# PowerStage.net
KiCad netlist of a schematic drawn in EAGLE
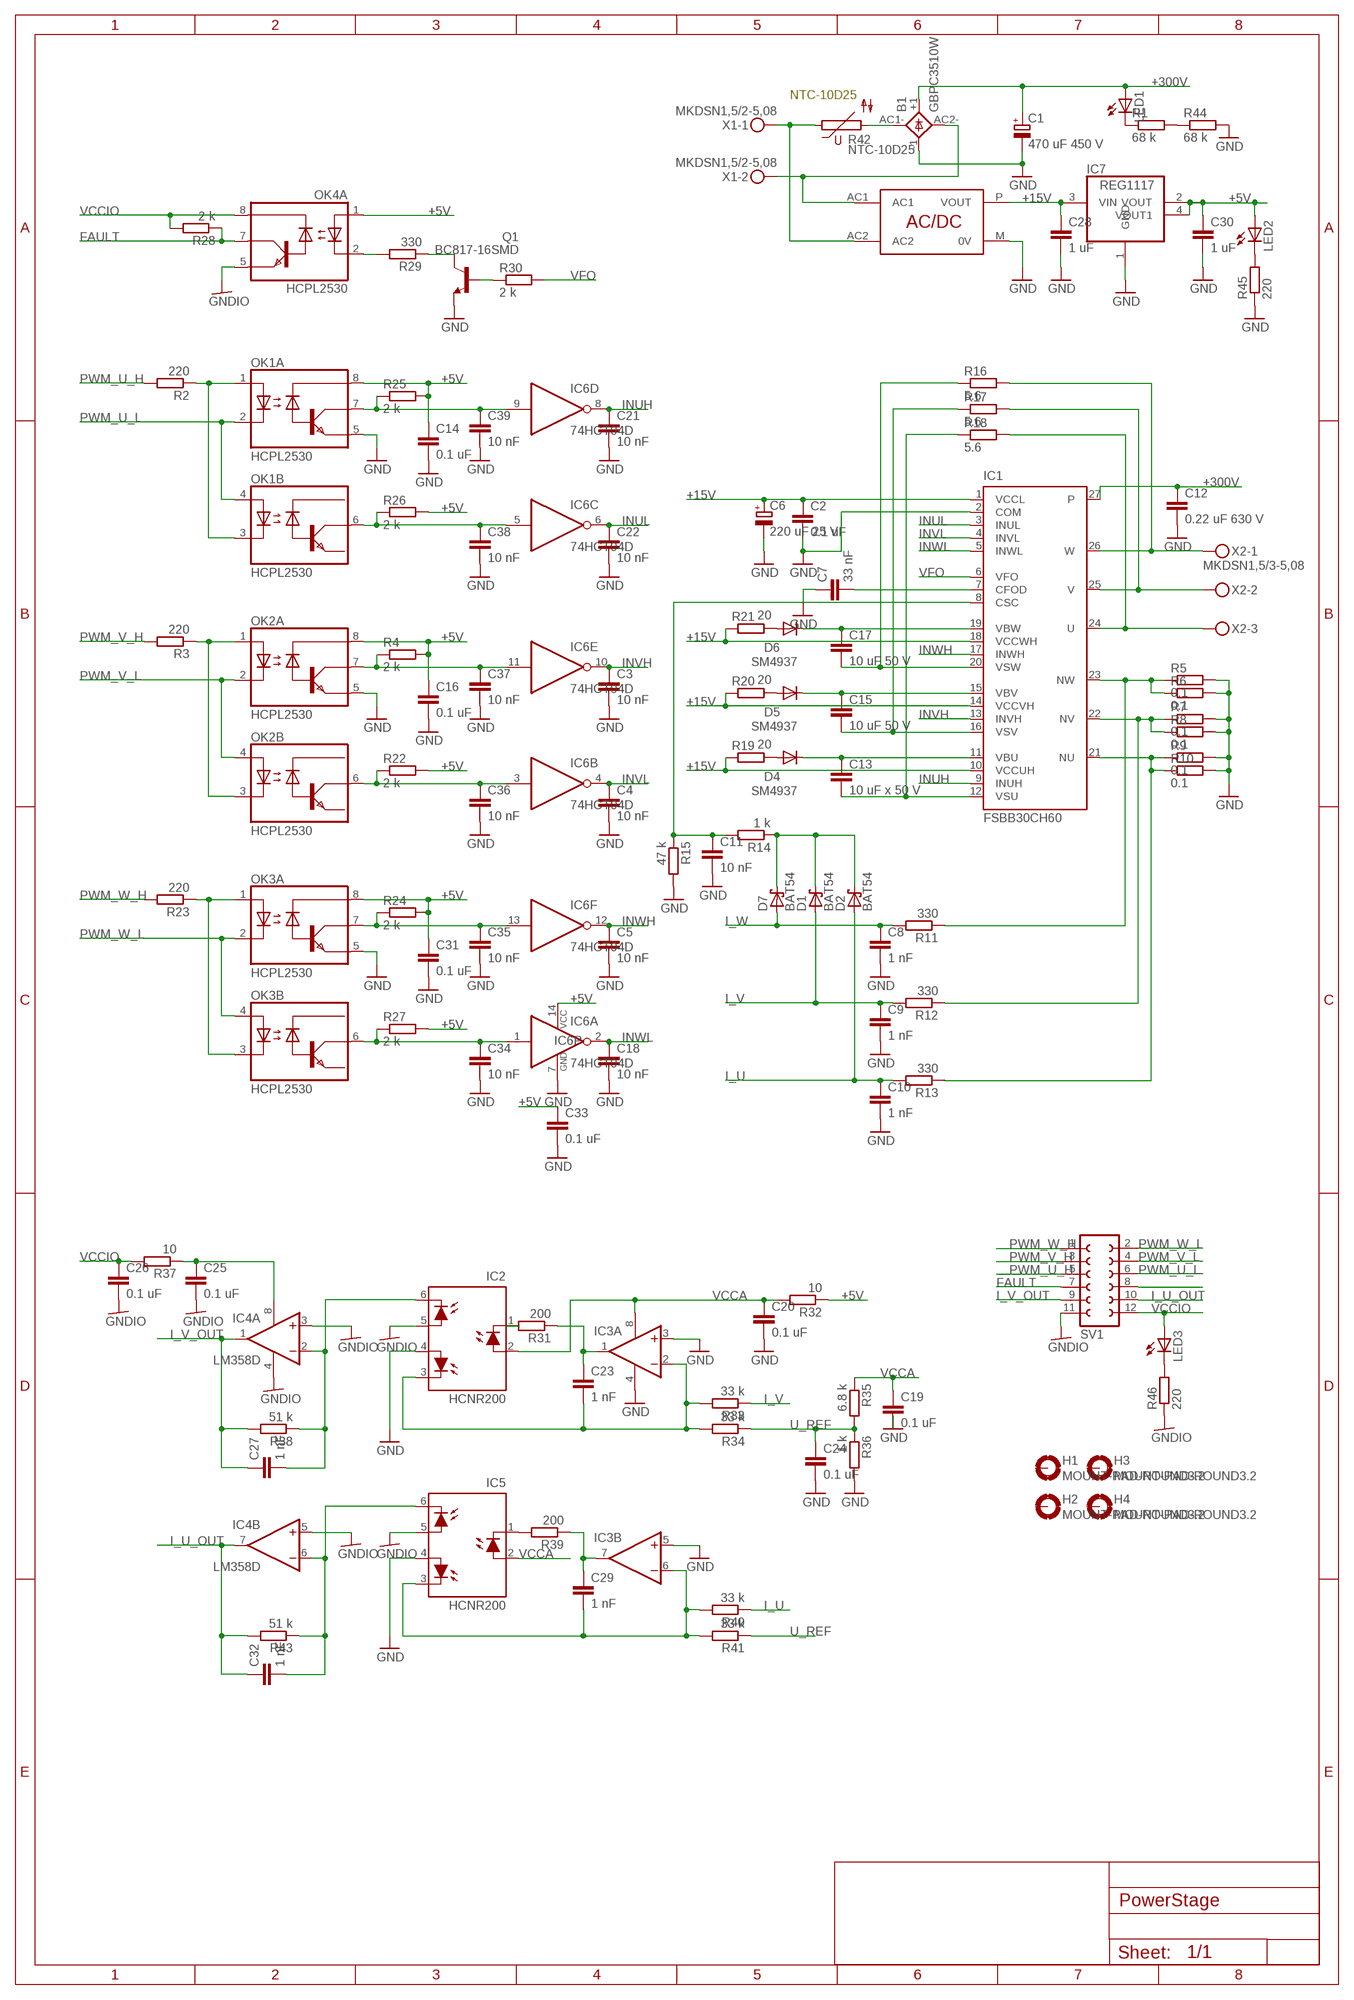
[diagram p0: schematic, sheet 1]

(export (version "E")
  (design (tool "Eeschema 10.0.6"))
  (components
    (comp (ref "B1")
      (value "GBPC3510W")
      (footprint "eagle-import:GBPC-W")
      (libsource (lib "eagle-import") (part "GBPC-W"))
    )
    (comp (ref "C1")
      (value "470 uF 450 V")
      (footprint "eagle-import:EB35D")
      (libsource (lib "eagle-import") (part "CPOL-EUE10-35"))
    )
    (comp (ref "C2")
      (value "0.1 uF")
      (footprint "eagle-import:C0603")
      (libsource (lib "eagle-import") (part "C-EUC0603"))
    )
    (comp (ref "C3")
      (value "10 nF")
      (footprint "eagle-import:C0603")
      (libsource (lib "eagle-import") (part "C-EUC0603"))
    )
    (comp (ref "C4")
      (value "10 nF")
      (footprint "eagle-import:C0603")
      (libsource (lib "eagle-import") (part "C-EUC0603"))
    )
    (comp (ref "C5")
      (value "10 nF")
      (footprint "eagle-import:C0603")
      (libsource (lib "eagle-import") (part "C-EUC0603"))
    )
    (comp (ref "C6")
      (value "220 uF 25 V")
      (footprint "eagle-import:PANASONIC_G")
      (libsource (lib "eagle-import") (part "CPOL-EUG"))
    )
    (comp (ref "C7")
      (value "33 nF")
      (footprint "eagle-import:C0603")
      (libsource (lib "eagle-import") (part "C-EUC0603"))
    )
    (comp (ref "C8")
      (value "1 nF")
      (footprint "eagle-import:C0603")
      (libsource (lib "eagle-import") (part "C-EUC0603"))
    )
    (comp (ref "C9")
      (value "1 nF")
      (footprint "eagle-import:C0603")
      (libsource (lib "eagle-import") (part "C-EUC0603"))
    )
    (comp (ref "C10")
      (value "1 nF")
      (footprint "eagle-import:C0603")
      (libsource (lib "eagle-import") (part "C-EUC0603"))
    )
    (comp (ref "C11")
      (value "10 nF")
      (footprint "eagle-import:C0603")
      (libsource (lib "eagle-import") (part "C-EUC0603"))
    )
    (comp (ref "C12")
      (value "0.22 uF 630 V")
      (footprint "eagle-import:C150-091X182")
      (libsource (lib "eagle-import") (part "C-EU150-091X182"))
    )
    (comp (ref "C13")
      (value "10 uF x 50 V")
      (footprint "eagle-import:C1210")
      (libsource (lib "eagle-import") (part "C-EUC1210"))
    )
    (comp (ref "C14")
      (value "0.1 uF")
      (footprint "eagle-import:C0603")
      (libsource (lib "eagle-import") (part "C-EUC0603"))
    )
    (comp (ref "C15")
      (value "10 uF 50 V")
      (footprint "eagle-import:C1210")
      (libsource (lib "eagle-import") (part "C-EUC1210"))
    )
    (comp (ref "C16")
      (value "0.1 uF")
      (footprint "eagle-import:C0603")
      (libsource (lib "eagle-import") (part "C-EUC0603"))
    )
    (comp (ref "C17")
      (value "10 uF 50 V")
      (footprint "eagle-import:C1210")
      (libsource (lib "eagle-import") (part "C-EUC1210"))
    )
    (comp (ref "C18")
      (value "10 nF")
      (footprint "eagle-import:C0603")
      (libsource (lib "eagle-import") (part "C-EUC0603"))
    )
    (comp (ref "C19")
      (value "0.1 uF")
      (footprint "eagle-import:C0603")
      (libsource (lib "eagle-import") (part "C-EUC0603"))
    )
    (comp (ref "C20")
      (value "0.1 uF")
      (footprint "eagle-import:C0603")
      (libsource (lib "eagle-import") (part "C-EUC0603"))
    )
    (comp (ref "C21")
      (value "10 nF")
      (footprint "eagle-import:C0603")
      (libsource (lib "eagle-import") (part "C-EUC0603"))
    )
    (comp (ref "C22")
      (value "10 nF")
      (footprint "eagle-import:C0603")
      (libsource (lib "eagle-import") (part "C-EUC0603"))
    )
    (comp (ref "C23")
      (value "1 nF")
      (footprint "eagle-import:C0603")
      (libsource (lib "eagle-import") (part "C-EUC0603"))
    )
    (comp (ref "C24")
      (value "0.1 uF")
      (footprint "eagle-import:C0603")
      (libsource (lib "eagle-import") (part "C-EUC0603"))
    )
    (comp (ref "C25")
      (value "0.1 uF")
      (footprint "eagle-import:C0603")
      (libsource (lib "eagle-import") (part "C-EUC0603"))
    )
    (comp (ref "C26")
      (value "0.1 uF")
      (footprint "eagle-import:C0603")
      (libsource (lib "eagle-import") (part "C-EUC0603"))
    )
    (comp (ref "C27")
      (value "1 nF")
      (footprint "eagle-import:C0603")
      (libsource (lib "eagle-import") (part "C-EUC0603"))
    )
    (comp (ref "C28")
      (value "1 uF")
      (footprint "eagle-import:C0603")
      (libsource (lib "eagle-import") (part "C-EUC0603"))
    )
    (comp (ref "C29")
      (value "1 nF")
      (footprint "eagle-import:C0603")
      (libsource (lib "eagle-import") (part "C-EUC0603"))
    )
    (comp (ref "C30")
      (value "1 uF")
      (footprint "eagle-import:C0603")
      (libsource (lib "eagle-import") (part "C-EUC0603"))
    )
    (comp (ref "C31")
      (value "0.1 uF")
      (footprint "eagle-import:C0603")
      (libsource (lib "eagle-import") (part "C-EUC0603"))
    )
    (comp (ref "C32")
      (value "1 nF")
      (footprint "eagle-import:C0603")
      (libsource (lib "eagle-import") (part "C-EUC0603"))
    )
    (comp (ref "C33")
      (value "0.1 uF")
      (footprint "eagle-import:C0603")
      (libsource (lib "eagle-import") (part "C-EUC0603"))
    )
    (comp (ref "C34")
      (value "10 nF")
      (footprint "eagle-import:C0603")
      (libsource (lib "eagle-import") (part "C-EUC0603"))
    )
    (comp (ref "C35")
      (value "10 nF")
      (footprint "eagle-import:C0603")
      (libsource (lib "eagle-import") (part "C-EUC0603"))
    )
    (comp (ref "C36")
      (value "10 nF")
      (footprint "eagle-import:C0603")
      (libsource (lib "eagle-import") (part "C-EUC0603"))
    )
    (comp (ref "C37")
      (value "10 nF")
      (footprint "eagle-import:C0603")
      (libsource (lib "eagle-import") (part "C-EUC0603"))
    )
    (comp (ref "C38")
      (value "10 nF")
      (footprint "eagle-import:C0603")
      (libsource (lib "eagle-import") (part "C-EUC0603"))
    )
    (comp (ref "C39")
      (value "10 nF")
      (footprint "eagle-import:C0603")
      (libsource (lib "eagle-import") (part "C-EUC0603"))
    )
    (comp (ref "D1")
      (value "BAT54")
      (footprint "eagle-import:SOT23")
      (libsource (lib "eagle-import") (part "BAT54"))
    )
    (comp (ref "D2")
      (value "BAT54")
      (footprint "eagle-import:SOT23")
      (libsource (lib "eagle-import") (part "BAT54"))
    )
    (comp (ref "D4")
      (value "SM4937")
      (footprint "eagle-import:MELF-MLL41")
      (libsource (lib "eagle-import") (part "DIODE-MELF-MLL41"))
    )
    (comp (ref "D5")
      (value "SM4937")
      (footprint "eagle-import:MELF-MLL41")
      (libsource (lib "eagle-import") (part "DIODE-MELF-MLL41"))
    )
    (comp (ref "D6")
      (value "SM4937")
      (footprint "eagle-import:MELF-MLL41")
      (libsource (lib "eagle-import") (part "DIODE-MELF-MLL41"))
    )
    (comp (ref "D7")
      (value "BAT54")
      (footprint "eagle-import:SOT23")
      (libsource (lib "eagle-import") (part "BAT54"))
    )
    (comp (ref "H1")
      (value "MOUNT-PAD-ROUND3.2")
      (footprint "eagle-import:3,2-PAD")
      (libsource (lib "eagle-import") (part "MOUNT-PAD-ROUND3.2"))
    )
    (comp (ref "H2")
      (value "MOUNT-PAD-ROUND3.2")
      (footprint "eagle-import:3,2-PAD")
      (libsource (lib "eagle-import") (part "MOUNT-PAD-ROUND3.2"))
    )
    (comp (ref "H3")
      (value "MOUNT-PAD-ROUND3.2")
      (footprint "eagle-import:3,2-PAD")
      (libsource (lib "eagle-import") (part "MOUNT-PAD-ROUND3.2"))
    )
    (comp (ref "H4")
      (value "MOUNT-PAD-ROUND3.2")
      (footprint "eagle-import:3,2-PAD")
      (libsource (lib "eagle-import") (part "MOUNT-PAD-ROUND3.2"))
    )
    (comp (ref "IC1")
      (value "FSBB30CH60")
      (footprint "eagle-import:FSBB30CH60")
      (fields (field (name "MPN") "FSBB30CH60B"))
      (libsource (lib "eagle-import") (part "FSBB30CH60"))
    )
    (comp (ref "IC2")
      (value "HCNR200")
      (footprint "eagle-import:DIL08-400")
      (libsource (lib "eagle-import") (part "HCNR200"))
    )
    (comp (ref "IC3")
      (value "2AMP_P8+4D")
      (footprint "eagle-import:SO08")
      (libsource (lib "eagle-import") (part "2AMP_P8+4D"))
    )
    (comp (ref "IC4")
      (value "LM358D")
      (footprint "eagle-import:SO08")
      (libsource (lib "eagle-import") (part "LM358D"))
    )
    (comp (ref "IC5")
      (value "HCNR200")
      (footprint "eagle-import:DIL08-400")
      (libsource (lib "eagle-import") (part "HCNR200"))
    )
    (comp (ref "IC6")
      (value "74HCT04D")
      (footprint "eagle-import:SO14")
      (libsource (lib "eagle-import") (part "7404DHCT"))
    )
    (comp (ref "IC7")
      (value "REG1117")
      (footprint "eagle-import:SOT223")
      (libsource (lib "eagle-import") (part "REG1117"))
    )
    (comp (ref "LED1")
      (value "LEDCHIP-LED0603")
      (footprint "eagle-import:CHIP-LED0603")
      (libsource (lib "eagle-import") (part "LEDCHIP-LED0603"))
    )
    (comp (ref "LED2")
      (value "LEDCHIP-LED0603")
      (footprint "eagle-import:CHIP-LED0603")
      (libsource (lib "eagle-import") (part "LEDCHIP-LED0603"))
    )
    (comp (ref "LED3")
      (value "LEDCHIP-LED0603")
      (footprint "eagle-import:CHIP-LED0603")
      (libsource (lib "eagle-import") (part "LEDCHIP-LED0603"))
    )
    (comp (ref "OK1")
      (value "HCPL2530")
      (footprint "eagle-import:DIL08")
      (fields (field (name "MF") "AGILENT TECHNOLOGIES") (field (name "MPN") "HCPL-2530-000E"))
      (libsource (lib "eagle-import") (part "HCPL2530"))
    )
    (comp (ref "OK2")
      (value "HCPL2530")
      (footprint "eagle-import:DIL08")
      (fields (field (name "MF") "AGILENT TECHNOLOGIES") (field (name "MPN") "HCPL-2530-000E"))
      (libsource (lib "eagle-import") (part "HCPL2530"))
    )
    (comp (ref "OK3")
      (value "HCPL2530")
      (footprint "eagle-import:DIL08")
      (fields (field (name "MF") "AGILENT TECHNOLOGIES") (field (name "MPN") "HCPL-2530-000E"))
      (libsource (lib "eagle-import") (part "HCPL2530"))
    )
    (comp (ref "OK4")
      (value "HCPL2530")
      (footprint "eagle-import:DIL08")
      (fields (field (name "MF") "AGILENT TECHNOLOGIES") (field (name "MPN") "HCPL-2530-000E"))
      (libsource (lib "eagle-import") (part "HCPL2530"))
    )
    (comp (ref "Q1")
      (value "BC817-16SMD")
      (footprint "eagle-import:SOT23-BEC")
      (libsource (lib "eagle-import") (part "BC817SMD-16"))
    )
    (comp (ref "R1")
      (value "68 k")
      (footprint "eagle-import:R1206")
      (libsource (lib "eagle-import") (part "resistor_R-EU_R1206"))
    )
    (comp (ref "R2")
      (value "220")
      (footprint "eagle-import:R0603")
      (libsource (lib "eagle-import") (part "R-EU_R0603"))
    )
    (comp (ref "R3")
      (value "220")
      (footprint "eagle-import:R0603")
      (libsource (lib "eagle-import") (part "R-EU_R0603"))
    )
    (comp (ref "R4")
      (value "2 k")
      (footprint "eagle-import:R0603")
      (libsource (lib "eagle-import") (part "R-EU_R0603"))
    )
    (comp (ref "R5")
      (value "0.1")
      (footprint "eagle-import:R2512")
      (libsource (lib "eagle-import") (part "R-EU_R2512"))
    )
    (comp (ref "R6")
      (value "0.1")
      (footprint "eagle-import:R2512")
      (libsource (lib "eagle-import") (part "R-EU_R2512"))
    )
    (comp (ref "R7")
      (value "0.1")
      (footprint "eagle-import:R2512")
      (libsource (lib "eagle-import") (part "R-EU_R2512"))
    )
    (comp (ref "R8")
      (value "0.1")
      (footprint "eagle-import:R2512")
      (libsource (lib "eagle-import") (part "R-EU_R2512"))
    )
    (comp (ref "R9")
      (value "0.1")
      (footprint "eagle-import:R2512")
      (libsource (lib "eagle-import") (part "R-EU_R2512"))
    )
    (comp (ref "R10")
      (value "0.1")
      (footprint "eagle-import:R2512")
      (libsource (lib "eagle-import") (part "R-EU_R2512"))
    )
    (comp (ref "R11")
      (value "330")
      (footprint "eagle-import:R0603")
      (libsource (lib "eagle-import") (part "R-EU_R0603"))
    )
    (comp (ref "R12")
      (value "330")
      (footprint "eagle-import:R0603")
      (libsource (lib "eagle-import") (part "R-EU_R0603"))
    )
    (comp (ref "R13")
      (value "330")
      (footprint "eagle-import:R0603")
      (libsource (lib "eagle-import") (part "R-EU_R0603"))
    )
    (comp (ref "R14")
      (value "1 k")
      (footprint "eagle-import:R0603")
      (libsource (lib "eagle-import") (part "R-EU_R0603"))
    )
    (comp (ref "R15")
      (value "47 k")
      (footprint "eagle-import:R0603")
      (libsource (lib "eagle-import") (part "R-EU_R0603"))
    )
    (comp (ref "R16")
      (value "5.6")
      (footprint "eagle-import:R1206")
      (libsource (lib "eagle-import") (part "R-EU_R1206"))
    )
    (comp (ref "R17")
      (value "5.6")
      (footprint "eagle-import:R1206")
      (libsource (lib "eagle-import") (part "R-EU_R1206"))
    )
    (comp (ref "R18")
      (value "5.6")
      (footprint "eagle-import:R1206")
      (libsource (lib "eagle-import") (part "R-EU_R1206"))
    )
    (comp (ref "R19")
      (value "20")
      (footprint "eagle-import:R1206")
      (libsource (lib "eagle-import") (part "R-EU_R1206"))
    )
    (comp (ref "R20")
      (value "20")
      (footprint "eagle-import:R1206")
      (libsource (lib "eagle-import") (part "R-EU_R1206"))
    )
    (comp (ref "R21")
      (value "20")
      (footprint "eagle-import:R1206")
      (libsource (lib "eagle-import") (part "R-EU_R1206"))
    )
    (comp (ref "R22")
      (value "2 k")
      (footprint "eagle-import:R0603")
      (libsource (lib "eagle-import") (part "R-EU_R0603"))
    )
    (comp (ref "R23")
      (value "220")
      (footprint "eagle-import:R0603")
      (libsource (lib "eagle-import") (part "R-EU_R0603"))
    )
    (comp (ref "R24")
      (value "2 k")
      (footprint "eagle-import:R0603")
      (libsource (lib "eagle-import") (part "R-EU_R0603"))
    )
    (comp (ref "R25")
      (value "2 k")
      (footprint "eagle-import:R0603")
      (libsource (lib "eagle-import") (part "R-EU_R0603"))
    )
    (comp (ref "R26")
      (value "2 k")
      (footprint "eagle-import:R0603")
      (libsource (lib "eagle-import") (part "R-EU_R0603"))
    )
    (comp (ref "R27")
      (value "2 k")
      (footprint "eagle-import:R0603")
      (libsource (lib "eagle-import") (part "R-EU_R0603"))
    )
    (comp (ref "R28")
      (value "2 k")
      (footprint "eagle-import:R0603")
      (libsource (lib "eagle-import") (part "R-EU_R0603"))
    )
    (comp (ref "R29")
      (value "330")
      (footprint "eagle-import:R0603")
      (libsource (lib "eagle-import") (part "R-EU_R0603"))
    )
    (comp (ref "R30")
      (value "2 k")
      (footprint "eagle-import:R0603")
      (libsource (lib "eagle-import") (part "R-EU_R0603"))
    )
    (comp (ref "R31")
      (value "200")
      (footprint "eagle-import:R0603")
      (libsource (lib "eagle-import") (part "R-EU_R0603"))
    )
    (comp (ref "R32")
      (value "10")
      (footprint "eagle-import:R0603")
      (libsource (lib "eagle-import") (part "R-EU_R0603"))
    )
    (comp (ref "R33")
      (value "33 k")
      (footprint "eagle-import:R0603")
      (libsource (lib "eagle-import") (part "R-EU_R0603"))
    )
    (comp (ref "R34")
      (value "33 k")
      (footprint "eagle-import:R0603")
      (libsource (lib "eagle-import") (part "R-EU_R0603"))
    )
    (comp (ref "R35")
      (value "6.8 k")
      (footprint "eagle-import:R0603")
      (libsource (lib "eagle-import") (part "R-EU_R0603"))
    )
    (comp (ref "R36")
      (value "1 k")
      (footprint "eagle-import:R0603")
      (libsource (lib "eagle-import") (part "R-EU_R0603"))
    )
    (comp (ref "R37")
      (value "10")
      (footprint "eagle-import:R0603")
      (libsource (lib "eagle-import") (part "R-EU_R0603"))
    )
    (comp (ref "R38")
      (value "51 k")
      (footprint "eagle-import:R0603")
      (libsource (lib "eagle-import") (part "R-EU_R0603"))
    )
    (comp (ref "R39")
      (value "200")
      (footprint "eagle-import:R0603")
      (libsource (lib "eagle-import") (part "R-EU_R0603"))
    )
    (comp (ref "R40")
      (value "33 k")
      (footprint "eagle-import:R0603")
      (libsource (lib "eagle-import") (part "R-EU_R0603"))
    )
    (comp (ref "R41")
      (value "33 k")
      (footprint "eagle-import:R0603")
      (libsource (lib "eagle-import") (part "R-EU_R0603"))
    )
    (comp (ref "R42")
      (value "NTC-10D25")
      (footprint "eagle-import:S20K40")
      (libsource (lib "eagle-import") (part "S20K40"))
    )
    (comp (ref "R43")
      (value "51 k")
      (footprint "eagle-import:R0603")
      (libsource (lib "eagle-import") (part "R-EU_R0603"))
    )
    (comp (ref "R44")
      (value "68 k")
      (footprint "eagle-import:R1206")
      (libsource (lib "eagle-import") (part "resistor_R-EU_R1206"))
    )
    (comp (ref "R45")
      (value "220")
      (footprint "eagle-import:R0603")
      (libsource (lib "eagle-import") (part "R-EU_R0603"))
    )
    (comp (ref "R46")
      (value "220")
      (footprint "eagle-import:R0603")
      (libsource (lib "eagle-import") (part "R-EU_R0603"))
    )
    (comp (ref "SV1")
      (value "FE06-2")
      (footprint "eagle-import:FE06-2")
      (libsource (lib "eagle-import") (part "FE06-2"))
    )
    (comp (ref "U$1")
      (value "KUUKO_090873")
      (footprint "eagle-import:KUUKO_090873")
      (libsource (lib "eagle-import") (part "KUUKO_090873"))
    )
    (comp (ref "X1")
      (value "MKDSN1,5/2-5,08")
      (footprint "eagle-import:MKDSN1,5_2-5,08")
      (fields (field (name "MPN") "MKDSN 1,5/2-5.08"))
      (libsource (lib "eagle-import") (part "MKDSN1,5/2-5,08"))
    )
    (comp (ref "X2")
      (value "MKDSN1,5/3-5,08")
      (footprint "eagle-import:MKDSN1,5_3-5,08")
      (fields (field (name "MPN") "SMKDSN1,5/3-5,08"))
      (libsource (lib "eagle-import") (part "MKDSN1,5/3-5,08"))
    )
  )
  (nets
    (net (code "1") (name "/+5V") (class "Default")
      (node (ref "C14") (pin "1") (pinfunction "1_1") (pintype "passive"))
      (node (ref "C16") (pin "1") (pinfunction "1_1") (pintype "passive"))
      (node (ref "C30") (pin "1") (pinfunction "1_1") (pintype "passive"))
      (node (ref "C31") (pin "1") (pinfunction "1_1") (pintype "passive"))
      (node (ref "C33") (pin "1") (pinfunction "1_1") (pintype "passive"))
      (node (ref "IC6") (pin "14") (pinfunction "VCC_14") (pintype "power_in"))
      (node (ref "IC7") (pin "2") (pinfunction "VOUT_2") (pintype "output"))
      (node (ref "IC7") (pin "4") (pinfunction "VOUT1_4") (pintype "output"))
      (node (ref "LED2") (pin "A") (pinfunction "A_A") (pintype "passive"))
      (node (ref "OK1") (pin "8") (pinfunction "VCC_8") (pintype "passive"))
      (node (ref "OK2") (pin "8") (pinfunction "VCC_8") (pintype "passive"))
      (node (ref "OK3") (pin "8") (pinfunction "VCC_8") (pintype "passive"))
      (node (ref "OK4") (pin "1") (pinfunction "A1_1") (pintype "passive"))
      (node (ref "R22") (pin "2") (pinfunction "2_2") (pintype "passive"))
      (node (ref "R24") (pin "2") (pinfunction "2_2") (pintype "passive"))
      (node (ref "R25") (pin "2") (pinfunction "2_2") (pintype "passive"))
      (node (ref "R26") (pin "2") (pinfunction "2_2") (pintype "passive"))
      (node (ref "R27") (pin "2") (pinfunction "2_2") (pintype "passive"))
      (node (ref "R32") (pin "1") (pinfunction "1_1") (pintype "passive"))
      (node (ref "R4") (pin "2") (pinfunction "2_2") (pintype "passive"))
    )
    (net (code "2") (name "/+15V") (class "Default")
      (node (ref "C2") (pin "1") (pinfunction "1_1") (pintype "passive"))
      (node (ref "C28") (pin "1") (pinfunction "1_1") (pintype "passive"))
      (node (ref "C6") (pin "+") (pinfunction "+_+") (pintype "passive"))
      (node (ref "IC1") (pin "1") (pinfunction "VCCL_1") (pintype "power_in"))
      (node (ref "IC1") (pin "10") (pinfunction "VCCUH_10") (pintype "input"))
      (node (ref "IC1") (pin "14") (pinfunction "VCCVH_14") (pintype "input"))
      (node (ref "IC1") (pin "18") (pinfunction "VCCWH_18") (pintype "input"))
      (node (ref "IC7") (pin "3") (pinfunction "VIN_3") (pintype "input"))
      (node (ref "R19") (pin "1") (pinfunction "1_1") (pintype "passive"))
      (node (ref "R20") (pin "1") (pinfunction "1_1") (pintype "passive"))
      (node (ref "R21") (pin "1") (pinfunction "1_1") (pintype "passive"))
      (node (ref "U$1") (pin "P") (pinfunction "VOUT_P") (pintype "bidirectional"))
    )
    (net (code "3") (name "/+300V") (class "Default")
      (node (ref "B1") (pin "+1") (pinfunction "+_+1") (pintype "passive"))
      (node (ref "C1") (pin "+") (pinfunction "+_+") (pintype "passive"))
      (node (ref "C12") (pin "1") (pinfunction "1_1") (pintype "passive"))
      (node (ref "IC1") (pin "27") (pinfunction "P_27") (pintype "input"))
      (node (ref "LED1") (pin "A") (pinfunction "A_A") (pintype "passive"))
    )
    (net (code "4") (name "/FAULT") (class "Default")
      (node (ref "OK4") (pin "7") (pinfunction "VO1_7") (pintype "passive"))
      (node (ref "R28") (pin "1") (pinfunction "1_1") (pintype "passive"))
      (node (ref "SV1") (pin "7") (pinfunction "7_7") (pintype "passive"))
    )
    (net (code "5") (name "/INUH") (class "Default")
      (node (ref "C21") (pin "1") (pinfunction "1_1") (pintype "passive"))
      (node (ref "IC1") (pin "9") (pinfunction "INUH_9") (pintype "input"))
      (node (ref "IC6") (pin "8") (pinfunction "O_8") (pintype "output"))
    )
    (net (code "6") (name "/INUL") (class "Default")
      (node (ref "C22") (pin "1") (pinfunction "1_1") (pintype "passive"))
      (node (ref "IC1") (pin "3") (pinfunction "INUL_3") (pintype "input"))
      (node (ref "IC6") (pin "6") (pinfunction "O_6") (pintype "output"))
    )
    (net (code "7") (name "/INVH") (class "Default")
      (node (ref "C3") (pin "1") (pinfunction "1_1") (pintype "passive"))
      (node (ref "IC1") (pin "13") (pinfunction "INVH_13") (pintype "input"))
      (node (ref "IC6") (pin "10") (pinfunction "O_10") (pintype "output"))
    )
    (net (code "8") (name "/INVL") (class "Default")
      (node (ref "C4") (pin "1") (pinfunction "1_1") (pintype "passive"))
      (node (ref "IC1") (pin "4") (pinfunction "INVL_4") (pintype "input"))
      (node (ref "IC6") (pin "4") (pinfunction "O_4") (pintype "output"))
    )
    (net (code "9") (name "/INWH") (class "Default")
      (node (ref "C5") (pin "1") (pinfunction "1_1") (pintype "passive"))
      (node (ref "IC1") (pin "17") (pinfunction "INWH_17") (pintype "input"))
      (node (ref "IC6") (pin "12") (pinfunction "O_12") (pintype "output"))
    )
    (net (code "10") (name "/INWL") (class "Default")
      (node (ref "C18") (pin "1") (pinfunction "1_1") (pintype "passive"))
      (node (ref "IC1") (pin "5") (pinfunction "INWL_5") (pintype "input"))
      (node (ref "IC6") (pin "2") (pinfunction "O_2") (pintype "output"))
    )
    (net (code "11") (name "/I_U") (class "Default")
      (node (ref "C10") (pin "1") (pinfunction "1_1") (pintype "passive"))
      (node (ref "D2") (pin "1") (pinfunction "A_1") (pintype "passive"))
      (node (ref "R13") (pin "2") (pinfunction "2_2") (pintype "passive"))
      (node (ref "R40") (pin "1") (pinfunction "1_1") (pintype "passive"))
    )
    (net (code "12") (name "/I_U_OUT") (class "Default")
      (node (ref "C32") (pin "1") (pinfunction "1_1") (pintype "passive"))
      (node (ref "IC4") (pin "7") (pinfunction "OUT_7") (pintype "output"))
      (node (ref "R43") (pin "2") (pinfunction "2_2") (pintype "passive"))
      (node (ref "SV1") (pin "10") (pinfunction "10_10") (pintype "passive"))
    )
    (net (code "13") (name "/I_V") (class "Default")
      (node (ref "C9") (pin "1") (pinfunction "1_1") (pintype "passive"))
      (node (ref "D1") (pin "1") (pinfunction "A_1") (pintype "passive"))
      (node (ref "R12") (pin "2") (pinfunction "2_2") (pintype "passive"))
      (node (ref "R33") (pin "1") (pinfunction "1_1") (pintype "passive"))
    )
    (net (code "14") (name "/I_V_OUT") (class "Default")
      (node (ref "C27") (pin "1") (pinfunction "1_1") (pintype "passive"))
      (node (ref "IC4") (pin "1") (pinfunction "OUT_1") (pintype "output"))
      (node (ref "R38") (pin "2") (pinfunction "2_2") (pintype "passive"))
      (node (ref "SV1") (pin "9") (pinfunction "9_9") (pintype "passive"))
    )
    (net (code "15") (name "/I_W") (class "Default")
      (node (ref "C8") (pin "1") (pinfunction "1_1") (pintype "passive"))
      (node (ref "D7") (pin "1") (pinfunction "A_1") (pintype "passive"))
      (node (ref "R11") (pin "2") (pinfunction "2_2") (pintype "passive"))
    )
    (net (code "16") (name "/PWM_U_H") (class "Default")
      (node (ref "R2") (pin "2") (pinfunction "2_2") (pintype "passive"))
      (node (ref "SV1") (pin "5") (pinfunction "5_5") (pintype "passive"))
    )
    (net (code "17") (name "/PWM_U_L") (class "Default")
      (node (ref "OK1") (pin "2") (pinfunction "C1_2") (pintype "passive"))
      (node (ref "OK1") (pin "4") (pinfunction "A2_4") (pintype "passive"))
      (node (ref "SV1") (pin "6") (pinfunction "6_6") (pintype "passive"))
    )
    (net (code "18") (name "/PWM_V_H") (class "Default")
      (node (ref "R3") (pin "2") (pinfunction "2_2") (pintype "passive"))
      (node (ref "SV1") (pin "3") (pinfunction "3_3") (pintype "passive"))
    )
    (net (code "19") (name "/PWM_V_L") (class "Default")
      (node (ref "OK2") (pin "2") (pinfunction "C1_2") (pintype "passive"))
      (node (ref "OK2") (pin "4") (pinfunction "A2_4") (pintype "passive"))
      (node (ref "SV1") (pin "4") (pinfunction "4_4") (pintype "passive"))
    )
    (net (code "20") (name "/PWM_W_H") (class "Default")
      (node (ref "R23") (pin "2") (pinfunction "2_2") (pintype "passive"))
      (node (ref "SV1") (pin "1") (pinfunction "1_1") (pintype "passive"))
    )
    (net (code "21") (name "/PWM_W_L") (class "Default")
      (node (ref "OK3") (pin "2") (pinfunction "C1_2") (pintype "passive"))
      (node (ref "OK3") (pin "4") (pinfunction "A2_4") (pintype "passive"))
      (node (ref "SV1") (pin "2") (pinfunction "2_2") (pintype "passive"))
    )
    (net (code "22") (name "/U_REF") (class "Default")
      (node (ref "C24") (pin "1") (pinfunction "1_1") (pintype "passive"))
      (node (ref "R34") (pin "1") (pinfunction "1_1") (pintype "passive"))
      (node (ref "R35") (pin "2") (pinfunction "2_2") (pintype "passive"))
      (node (ref "R36") (pin "1") (pinfunction "1_1") (pintype "passive"))
      (node (ref "R41") (pin "1") (pinfunction "1_1") (pintype "passive"))
    )
    (net (code "23") (name "/VCCA") (class "Default")
      (node (ref "C19") (pin "1") (pinfunction "1_1") (pintype "passive"))
      (node (ref "C20") (pin "1") (pinfunction "1_1") (pintype "passive"))
      (node (ref "IC2") (pin "2") (pinfunction "A_2") (pintype "passive"))
      (node (ref "IC3") (pin "8") (pinfunction "V+_8") (pintype "power_in"))
      (node (ref "IC5") (pin "2") (pinfunction "A_2") (pintype "passive"))
      (node (ref "R32") (pin "2") (pinfunction "2_2") (pintype "passive"))
      (node (ref "R35") (pin "1") (pinfunction "1_1") (pintype "passive"))
    )
    (net (code "24") (name "/VCCIO") (class "Default")
      (node (ref "C26") (pin "1") (pinfunction "1_1") (pintype "passive"))
      (node (ref "LED3") (pin "A") (pinfunction "A_A") (pintype "passive"))
      (node (ref "OK4") (pin "8") (pinfunction "VCC_8") (pintype "passive"))
      (node (ref "R28") (pin "2") (pinfunction "2_2") (pintype "passive"))
      (node (ref "R37") (pin "2") (pinfunction "2_2") (pintype "passive"))
      (node (ref "SV1") (pin "12") (pinfunction "12_12") (pintype "passive"))
    )
    (net (code "25") (name "/VFO") (class "Default")
      (node (ref "IC1") (pin "6") (pinfunction "VFO_6") (pintype "output"))
      (node (ref "R30") (pin "2") (pinfunction "2_2") (pintype "passive"))
    )
    (net (code "26") (name "GND") (class "Default")
      (node (ref "B1") (pin "-1") (pinfunction "-_-1") (pintype "passive"))
      (node (ref "C1") (pin "-") (pinfunction "-_-") (pintype "passive"))
      (node (ref "C10") (pin "2") (pinfunction "2_2") (pintype "passive"))
      (node (ref "C11") (pin "2") (pinfunction "2_2") (pintype "passive"))
      (node (ref "C12") (pin "2") (pinfunction "2_2") (pintype "passive"))
      (node (ref "C14") (pin "2") (pinfunction "2_2") (pintype "passive"))
      (node (ref "C16") (pin "2") (pinfunction "2_2") (pintype "passive"))
      (node (ref "C18") (pin "2") (pinfunction "2_2") (pintype "passive"))
      (node (ref "C19") (pin "2") (pinfunction "2_2") (pintype "passive"))
      (node (ref "C2") (pin "2") (pinfunction "2_2") (pintype "passive"))
      (node (ref "C20") (pin "2") (pinfunction "2_2") (pintype "passive"))
      (node (ref "C21") (pin "2") (pinfunction "2_2") (pintype "passive"))
      (node (ref "C22") (pin "2") (pinfunction "2_2") (pintype "passive"))
      (node (ref "C24") (pin "2") (pinfunction "2_2") (pintype "passive"))
      (node (ref "C28") (pin "2") (pinfunction "2_2") (pintype "passive"))
      (node (ref "C3") (pin "2") (pinfunction "2_2") (pintype "passive"))
      (node (ref "C30") (pin "2") (pinfunction "2_2") (pintype "passive"))
      (node (ref "C31") (pin "2") (pinfunction "2_2") (pintype "passive"))
      (node (ref "C33") (pin "2") (pinfunction "2_2") (pintype "passive"))
      (node (ref "C34") (pin "2") (pinfunction "2_2") (pintype "passive"))
      (node (ref "C35") (pin "2") (pinfunction "2_2") (pintype "passive"))
      (node (ref "C36") (pin "2") (pinfunction "2_2") (pintype "passive"))
      (node (ref "C37") (pin "2") (pinfunction "2_2") (pintype "passive"))
      (node (ref "C38") (pin "2") (pinfunction "2_2") (pintype "passive"))
      (node (ref "C39") (pin "2") (pinfunction "2_2") (pintype "passive"))
      (node (ref "C4") (pin "2") (pinfunction "2_2") (pintype "passive"))
      (node (ref "C5") (pin "2") (pinfunction "2_2") (pintype "passive"))
      (node (ref "C6") (pin "-") (pinfunction "-_-") (pintype "passive"))
      (node (ref "C7") (pin "1") (pinfunction "1_1") (pintype "passive"))
      (node (ref "C8") (pin "2") (pinfunction "2_2") (pintype "passive"))
      (node (ref "C9") (pin "2") (pinfunction "2_2") (pintype "passive"))
      (node (ref "IC1") (pin "2") (pinfunction "COM_2") (pintype "power_in"))
      (node (ref "IC2") (pin "4") (pinfunction "A1_4") (pintype "passive"))
      (node (ref "IC3") (pin "3") (pinfunction "+IN_3") (pintype "input"))
      (node (ref "IC3") (pin "4") (pinfunction "V-_4") (pintype "power_in"))
      (node (ref "IC3") (pin "5") (pinfunction "+IN_5") (pintype "input"))
      (node (ref "IC5") (pin "4") (pinfunction "A1_4") (pintype "passive"))
      (node (ref "IC6") (pin "7") (pinfunction "GND_7") (pintype "power_in"))
      (node (ref "IC7") (pin "1") (pinfunction "GND_1") (pintype "power_in"))
      (node (ref "OK1") (pin "5") (pinfunction "GND_5") (pintype "passive"))
      (node (ref "OK2") (pin "5") (pinfunction "GND_5") (pintype "passive"))
      (node (ref "OK3") (pin "5") (pinfunction "GND_5") (pintype "passive"))
      (node (ref "Q1") (pin "E") (pinfunction "E_E") (pintype "passive"))
      (node (ref "R10") (pin "2") (pinfunction "2_2") (pintype "passive"))
      (node (ref "R15") (pin "2") (pinfunction "2_2") (pintype "passive"))
      (node (ref "R36") (pin "2") (pinfunction "2_2") (pintype "passive"))
      (node (ref "R44") (pin "2") (pinfunction "2_2") (pintype "passive"))
      (node (ref "R45") (pin "1") (pinfunction "1_1") (pintype "passive"))
      (node (ref "R5") (pin "2") (pinfunction "2_2") (pintype "passive"))
      (node (ref "R6") (pin "2") (pinfunction "2_2") (pintype "passive"))
      (node (ref "R7") (pin "2") (pinfunction "2_2") (pintype "passive"))
      (node (ref "R8") (pin "2") (pinfunction "2_2") (pintype "passive"))
      (node (ref "R9") (pin "2") (pinfunction "2_2") (pintype "passive"))
      (node (ref "U$1") (pin "M") (pinfunction "0V_M") (pintype "bidirectional"))
    )
    (net (code "27") (name "GNDIO") (class "Default")
      (node (ref "C25") (pin "2") (pinfunction "2_2") (pintype "passive"))
      (node (ref "C26") (pin "2") (pinfunction "2_2") (pintype "passive"))
      (node (ref "IC2") (pin "5") (pinfunction "A2_5") (pintype "passive"))
      (node (ref "IC4") (pin "3") (pinfunction "+IN_3") (pintype "input"))
      (node (ref "IC4") (pin "4") (pinfunction "V-_4") (pintype "power_in"))
      (node (ref "IC4") (pin "5") (pinfunction "+IN_5") (pintype "input"))
      (node (ref "IC5") (pin "5") (pinfunction "A2_5") (pintype "passive"))
      (node (ref "OK4") (pin "5") (pinfunction "GND_5") (pintype "passive"))
      (node (ref "R46") (pin "1") (pinfunction "1_1") (pintype "passive"))
      (node (ref "SV1") (pin "11") (pinfunction "11_11") (pintype "passive"))
    )
    (net (code "28") (name "Net-(B1-AC1)") (class "Default")
      (node (ref "B1") (pin "AC1-") (pinfunction "AC1_AC1-") (pintype "passive"))
      (node (ref "R42") (pin "2") (pinfunction "2_2") (pintype "passive"))
    )
    (net (code "29") (name "Net-(B1-AC2)") (class "Default")
      (node (ref "B1") (pin "AC2-") (pinfunction "AC2_AC2-") (pintype "passive"))
      (node (ref "U$1") (pin "AC1") (pinfunction "AC1_AC1") (pintype "bidirectional"))
      (node (ref "X1") (pin "2") (pinfunction "KL_2") (pintype "passive"))
    )
    (net (code "30") (name "Net-(D1-C)") (class "Default")
      (node (ref "D1") (pin "3") (pinfunction "C_3") (pintype "passive"))
      (node (ref "D2") (pin "3") (pinfunction "C_3") (pintype "passive"))
      (node (ref "D7") (pin "3") (pinfunction "C_3") (pintype "passive"))
      (node (ref "R14") (pin "1") (pinfunction "1_1") (pintype "passive"))
    )
    (net (code "31") (name "Net-(D4-PadA)") (class "Default")
      (node (ref "D4") (pin "A") (pinfunction "A_A") (pintype "passive"))
      (node (ref "R19") (pin "2") (pinfunction "2_2") (pintype "passive"))
    )
    (net (code "32") (name "Net-(D5-PadA)") (class "Default")
      (node (ref "D5") (pin "A") (pinfunction "A_A") (pintype "passive"))
      (node (ref "R20") (pin "2") (pinfunction "2_2") (pintype "passive"))
    )
    (net (code "33") (name "Net-(D6-PadA)") (class "Default")
      (node (ref "D6") (pin "A") (pinfunction "A_A") (pintype "passive"))
      (node (ref "R21") (pin "2") (pinfunction "2_2") (pintype "passive"))
    )
    (net (code "34") (name "Net-(IC1-CFOD)") (class "Default")
      (node (ref "C7") (pin "2") (pinfunction "2_2") (pintype "passive"))
      (node (ref "IC1") (pin "7") (pinfunction "CFOD_7") (pintype "passive"))
    )
    (net (code "35") (name "Net-(IC1-CSC)") (class "Default")
      (node (ref "C11") (pin "1") (pinfunction "1_1") (pintype "passive"))
      (node (ref "IC1") (pin "8") (pinfunction "CSC_8") (pintype "passive"))
      (node (ref "R14") (pin "2") (pinfunction "2_2") (pintype "passive"))
      (node (ref "R15") (pin "1") (pinfunction "1_1") (pintype "passive"))
    )
    (net (code "36") (name "Net-(IC1-NU)") (class "Default")
      (node (ref "IC1") (pin "21") (pinfunction "NU_21") (pintype "input"))
      (node (ref "R10") (pin "1") (pinfunction "1_1") (pintype "passive"))
      (node (ref "R13") (pin "1") (pinfunction "1_1") (pintype "passive"))
      (node (ref "R9") (pin "1") (pinfunction "1_1") (pintype "passive"))
    )
    (net (code "37") (name "Net-(IC1-NV)") (class "Default")
      (node (ref "IC1") (pin "22") (pinfunction "NV_22") (pintype "input"))
      (node (ref "R12") (pin "1") (pinfunction "1_1") (pintype "passive"))
      (node (ref "R7") (pin "1") (pinfunction "1_1") (pintype "passive"))
      (node (ref "R8") (pin "1") (pinfunction "1_1") (pintype "passive"))
    )
    (net (code "38") (name "Net-(IC1-NW)") (class "Default")
      (node (ref "IC1") (pin "23") (pinfunction "NW_23") (pintype "input"))
      (node (ref "R11") (pin "1") (pinfunction "1_1") (pintype "passive"))
      (node (ref "R5") (pin "1") (pinfunction "1_1") (pintype "passive"))
      (node (ref "R6") (pin "1") (pinfunction "1_1") (pintype "passive"))
    )
    (net (code "39") (name "Net-(IC1-U)") (class "Default")
      (node (ref "IC1") (pin "24") (pinfunction "U_24") (pintype "output"))
      (node (ref "R18") (pin "2") (pinfunction "2_2") (pintype "passive"))
      (node (ref "X2") (pin "3") (pinfunction "KL_3") (pintype "passive"))
    )
    (net (code "40") (name "Net-(IC1-V)") (class "Default")
      (node (ref "IC1") (pin "25") (pinfunction "V_25") (pintype "output"))
      (node (ref "R17") (pin "2") (pinfunction "2_2") (pintype "passive"))
      (node (ref "X2") (pin "2") (pinfunction "KL_2") (pintype "passive"))
    )
    (net (code "41") (name "Net-(IC1-VBU)") (class "Default")
      (node (ref "C13") (pin "1") (pinfunction "1_1") (pintype "passive"))
      (node (ref "D4") (pin "C") (pinfunction "C_C") (pintype "passive"))
      (node (ref "IC1") (pin "11") (pinfunction "VBU_11") (pintype "input"))
    )
    (net (code "42") (name "Net-(IC1-VBV)") (class "Default")
      (node (ref "C15") (pin "1") (pinfunction "1_1") (pintype "passive"))
      (node (ref "D5") (pin "C") (pinfunction "C_C") (pintype "passive"))
      (node (ref "IC1") (pin "15") (pinfunction "VBV_15") (pintype "input"))
    )
    (net (code "43") (name "Net-(IC1-VBW)") (class "Default")
      (node (ref "C17") (pin "1") (pinfunction "1_1") (pintype "passive"))
      (node (ref "D6") (pin "C") (pinfunction "C_C") (pintype "passive"))
      (node (ref "IC1") (pin "19") (pinfunction "VBW_19") (pintype "input"))
    )
    (net (code "44") (name "Net-(IC1-VSU)") (class "Default")
      (node (ref "C13") (pin "2") (pinfunction "2_2") (pintype "passive"))
      (node (ref "IC1") (pin "12") (pinfunction "VSU_12") (pintype "input"))
      (node (ref "R18") (pin "1") (pinfunction "1_1") (pintype "passive"))
    )
    (net (code "45") (name "Net-(IC1-VSV)") (class "Default")
      (node (ref "C15") (pin "2") (pinfunction "2_2") (pintype "passive"))
      (node (ref "IC1") (pin "16") (pinfunction "VSV_16") (pintype "input"))
      (node (ref "R17") (pin "1") (pinfunction "1_1") (pintype "passive"))
    )
    (net (code "46") (name "Net-(IC1-VSW)") (class "Default")
      (node (ref "C17") (pin "2") (pinfunction "2_2") (pintype "passive"))
      (node (ref "IC1") (pin "20") (pinfunction "VSW_20") (pintype "input"))
      (node (ref "R16") (pin "1") (pinfunction "1_1") (pintype "passive"))
    )
    (net (code "47") (name "Net-(IC1-W)") (class "Default")
      (node (ref "IC1") (pin "26") (pinfunction "W_26") (pintype "output"))
      (node (ref "R16") (pin "2") (pinfunction "2_2") (pintype "passive"))
      (node (ref "X2") (pin "1") (pinfunction "KL_1") (pintype "passive"))
    )
    (net (code "48") (name "Net-(IC2-C)") (class "Default")
      (node (ref "IC2") (pin "1") (pinfunction "C_1") (pintype "passive"))
      (node (ref "R31") (pin "2") (pinfunction "2_2") (pintype "passive"))
    )
    (net (code "49") (name "Net-(IC2-C1)") (class "Default")
      (node (ref "C23") (pin "2") (pinfunction "2_2") (pintype "passive"))
      (node (ref "IC2") (pin "3") (pinfunction "C1_3") (pintype "passive"))
      (node (ref "IC3") (pin "2") (pinfunction "-IN_2") (pintype "input"))
      (node (ref "R33") (pin "2") (pinfunction "2_2") (pintype "passive"))
      (node (ref "R34") (pin "2") (pinfunction "2_2") (pintype "passive"))
    )
    (net (code "50") (name "Net-(IC2-C2)") (class "Default")
      (node (ref "C27") (pin "2") (pinfunction "2_2") (pintype "passive"))
      (node (ref "IC2") (pin "6") (pinfunction "C2_6") (pintype "passive"))
      (node (ref "IC4") (pin "2") (pinfunction "-IN_2") (pintype "input"))
      (node (ref "R38") (pin "1") (pinfunction "1_1") (pintype "passive"))
    )
    (net (code "51") (name "Net-(IC3A-OUT)") (class "Default")
      (node (ref "C23") (pin "1") (pinfunction "1_1") (pintype "passive"))
      (node (ref "IC3") (pin "1") (pinfunction "OUT_1") (pintype "output"))
      (node (ref "R31") (pin "1") (pinfunction "1_1") (pintype "passive"))
    )
    (net (code "52") (name "Net-(IC3B--IN)") (class "Default")
      (node (ref "C29") (pin "2") (pinfunction "2_2") (pintype "passive"))
      (node (ref "IC3") (pin "6") (pinfunction "-IN_6") (pintype "input"))
      (node (ref "IC5") (pin "3") (pinfunction "C1_3") (pintype "passive"))
      (node (ref "R40") (pin "2") (pinfunction "2_2") (pintype "passive"))
      (node (ref "R41") (pin "2") (pinfunction "2_2") (pintype "passive"))
    )
    (net (code "53") (name "Net-(IC3B-OUT)") (class "Default")
      (node (ref "C29") (pin "1") (pinfunction "1_1") (pintype "passive"))
      (node (ref "IC3") (pin "7") (pinfunction "OUT_7") (pintype "output"))
      (node (ref "R39") (pin "1") (pinfunction "1_1") (pintype "passive"))
    )
    (net (code "54") (name "Net-(IC4B--IN)") (class "Default")
      (node (ref "C32") (pin "2") (pinfunction "2_2") (pintype "passive"))
      (node (ref "IC4") (pin "6") (pinfunction "-IN_6") (pintype "input"))
      (node (ref "IC5") (pin "6") (pinfunction "C2_6") (pintype "passive"))
      (node (ref "R43") (pin "1") (pinfunction "1_1") (pintype "passive"))
    )
    (net (code "55") (name "Net-(IC4C-V+)") (class "Default")
      (node (ref "C25") (pin "1") (pinfunction "1_1") (pintype "passive"))
      (node (ref "IC4") (pin "8") (pinfunction "V+_8") (pintype "power_in"))
      (node (ref "R37") (pin "1") (pinfunction "1_1") (pintype "passive"))
    )
    (net (code "56") (name "Net-(IC5-C)") (class "Default")
      (node (ref "IC5") (pin "1") (pinfunction "C_1") (pintype "passive"))
      (node (ref "R39") (pin "2") (pinfunction "2_2") (pintype "passive"))
    )
    (net (code "57") (name "Net-(IC6A-I)") (class "Default")
      (node (ref "C34") (pin "1") (pinfunction "1_1") (pintype "passive"))
      (node (ref "IC6") (pin "1") (pinfunction "I_1") (pintype "input"))
      (node (ref "OK3") (pin "6") (pinfunction "VO2_6") (pintype "passive"))
      (node (ref "R27") (pin "1") (pinfunction "1_1") (pintype "passive"))
    )
    (net (code "58") (name "Net-(IC6B-I)") (class "Default")
      (node (ref "C36") (pin "1") (pinfunction "1_1") (pintype "passive"))
      (node (ref "IC6") (pin "3") (pinfunction "I_3") (pintype "input"))
      (node (ref "OK2") (pin "6") (pinfunction "VO2_6") (pintype "passive"))
      (node (ref "R22") (pin "1") (pinfunction "1_1") (pintype "passive"))
    )
    (net (code "59") (name "Net-(IC6C-I)") (class "Default")
      (node (ref "C38") (pin "1") (pinfunction "1_1") (pintype "passive"))
      (node (ref "IC6") (pin "5") (pinfunction "I_5") (pintype "input"))
      (node (ref "OK1") (pin "6") (pinfunction "VO2_6") (pintype "passive"))
      (node (ref "R26") (pin "1") (pinfunction "1_1") (pintype "passive"))
    )
    (net (code "60") (name "Net-(IC6D-I)") (class "Default")
      (node (ref "C39") (pin "1") (pinfunction "1_1") (pintype "passive"))
      (node (ref "IC6") (pin "9") (pinfunction "I_9") (pintype "input"))
      (node (ref "OK1") (pin "7") (pinfunction "VO1_7") (pintype "passive"))
      (node (ref "R25") (pin "1") (pinfunction "1_1") (pintype "passive"))
    )
    (net (code "61") (name "Net-(IC6E-I)") (class "Default")
      (node (ref "C37") (pin "1") (pinfunction "1_1") (pintype "passive"))
      (node (ref "IC6") (pin "11") (pinfunction "I_11") (pintype "input"))
      (node (ref "OK2") (pin "7") (pinfunction "VO1_7") (pintype "passive"))
      (node (ref "R4") (pin "1") (pinfunction "1_1") (pintype "passive"))
    )
    (net (code "62") (name "Net-(IC6F-I)") (class "Default")
      (node (ref "C35") (pin "1") (pinfunction "1_1") (pintype "passive"))
      (node (ref "IC6") (pin "13") (pinfunction "I_13") (pintype "input"))
      (node (ref "OK3") (pin "7") (pinfunction "VO1_7") (pintype "passive"))
      (node (ref "R24") (pin "1") (pinfunction "1_1") (pintype "passive"))
    )
    (net (code "63") (name "Net-(LED1-PadC)") (class "Default")
      (node (ref "LED1") (pin "C") (pinfunction "C_C") (pintype "passive"))
      (node (ref "R1") (pin "1") (pinfunction "1_1") (pintype "passive"))
    )
    (net (code "64") (name "Net-(LED2-PadC)") (class "Default")
      (node (ref "LED2") (pin "C") (pinfunction "C_C") (pintype "passive"))
      (node (ref "R45") (pin "2") (pinfunction "2_2") (pintype "passive"))
    )
    (net (code "65") (name "Net-(LED3-PadC)") (class "Default")
      (node (ref "LED3") (pin "C") (pinfunction "C_C") (pintype "passive"))
      (node (ref "R46") (pin "2") (pinfunction "2_2") (pintype "passive"))
    )
    (net (code "66") (name "Net-(OK1A-A1)") (class "Default")
      (node (ref "OK1") (pin "1") (pinfunction "A1_1") (pintype "passive"))
      (node (ref "OK1") (pin "3") (pinfunction "C2_3") (pintype "passive"))
      (node (ref "R2") (pin "1") (pinfunction "1_1") (pintype "passive"))
    )
    (net (code "67") (name "Net-(OK2A-A1)") (class "Default")
      (node (ref "OK2") (pin "1") (pinfunction "A1_1") (pintype "passive"))
      (node (ref "OK2") (pin "3") (pinfunction "C2_3") (pintype "passive"))
      (node (ref "R3") (pin "1") (pinfunction "1_1") (pintype "passive"))
    )
    (net (code "68") (name "Net-(OK3A-A1)") (class "Default")
      (node (ref "OK3") (pin "1") (pinfunction "A1_1") (pintype "passive"))
      (node (ref "OK3") (pin "3") (pinfunction "C2_3") (pintype "passive"))
      (node (ref "R23") (pin "1") (pinfunction "1_1") (pintype "passive"))
    )
    (net (code "69") (name "Net-(OK4A-C1)") (class "Default")
      (node (ref "OK4") (pin "2") (pinfunction "C1_2") (pintype "passive"))
      (node (ref "R29") (pin "2") (pinfunction "2_2") (pintype "passive"))
    )
    (net (code "70") (name "Net-(Q1-PadB)") (class "Default")
      (node (ref "Q1") (pin "B") (pinfunction "B_B") (pintype "passive"))
      (node (ref "R30") (pin "1") (pinfunction "1_1") (pintype "passive"))
    )
    (net (code "71") (name "Net-(Q1-PadC)") (class "Default")
      (node (ref "Q1") (pin "C") (pinfunction "C_C") (pintype "passive"))
      (node (ref "R29") (pin "1") (pinfunction "1_1") (pintype "passive"))
    )
    (net (code "72") (name "Net-(R1-Pad2)") (class "Default")
      (node (ref "R1") (pin "2") (pinfunction "2_2") (pintype "passive"))
      (node (ref "R44") (pin "1") (pinfunction "1_1") (pintype "passive"))
    )
    (net (code "73") (name "Net-(X1A-KL)") (class "Default")
      (node (ref "R42") (pin "1") (pinfunction "1_1") (pintype "passive"))
      (node (ref "U$1") (pin "AC2") (pinfunction "AC2_AC2") (pintype "bidirectional"))
      (node (ref "X1") (pin "1") (pinfunction "KL_1") (pintype "passive"))
    )
    (net (code "74") (name "unconnected-(H1-MOUNT-PadB3,2)") (class "Default")
      (node (ref "H1") (pin "B3,2") (pinfunction "MOUNT_B3,2") (pintype "passive"))
    )
    (net (code "75") (name "unconnected-(H2-MOUNT-PadB3,2)") (class "Default")
      (node (ref "H2") (pin "B3,2") (pinfunction "MOUNT_B3,2") (pintype "passive"))
    )
    (net (code "76") (name "unconnected-(H3-MOUNT-PadB3,2)") (class "Default")
      (node (ref "H3") (pin "B3,2") (pinfunction "MOUNT_B3,2") (pintype "passive"))
    )
    (net (code "77") (name "unconnected-(H4-MOUNT-PadB3,2)") (class "Default")
      (node (ref "H4") (pin "B3,2") (pinfunction "MOUNT_B3,2") (pintype "passive"))
    )
    (net (code "78") (name "unconnected-(SV1-Pad8)") (class "Default")
      (node (ref "SV1") (pin "8") (pinfunction "8_8") (pintype "passive"))
    )
  )
)
